# Processor_Interface.net
KiCad netlist of a schematic drawn in Altium Designer
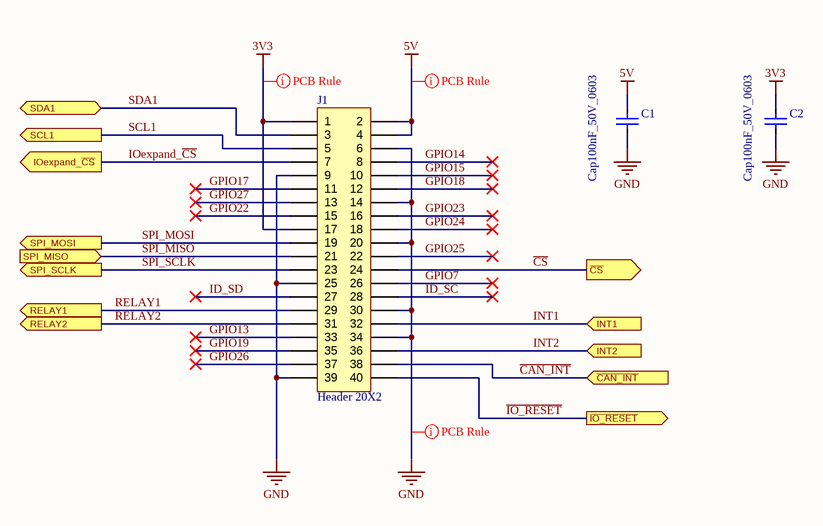
[diagram p0:  Processor_Interface.SchDoc]

(export (version "E")
  (design (tool "Eeschema 10.0.6"))
  (components
    (comp (ref "C1")
      (value "Cap100nF_50V_0603")
      (footprint "0603C_L")
      (libsource (lib "Advanced] Training Course - A365") (part "CAP General"))
    )
    (comp (ref "C2")
      (value "Cap100nF_50V_0603")
      (footprint "0603C_L")
      (libsource (lib "Advanced] Training Course - A365") (part "CAP General"))
    )
    (comp (ref "J1")
      (value "Header 20X2")
      (footprint "HDR2X20")
      (description "Header, 20-Pin, Dual row")
      (fields (field (name "PUBLISHER") "Altium Limited") (field (name "SOURCE") "WCT.SchLib"))
      (libsource (lib "Advanced] Training Course - A365") (part "Header 20X2"))
    )
  )
  (nets
    (net (code "1") (name "/CAN_INT") (class "Default")
      (node (ref "J1") (pin "38") (pinfunction "38_38") (pintype "passive"))
    )
    (net (code "2") (name "/GPIO7") (class "Default")
      (node (ref "J1") (pin "26") (pinfunction "26_26") (pintype "passive+no_connect"))
    )
    (net (code "3") (name "/GPIO13") (class "Default")
      (node (ref "J1") (pin "33") (pinfunction "33_33") (pintype "passive+no_connect"))
    )
    (net (code "4") (name "/GPIO14") (class "Default")
      (node (ref "J1") (pin "8") (pinfunction "8_8") (pintype "passive+no_connect"))
    )
    (net (code "5") (name "/GPIO15") (class "Default")
      (node (ref "J1") (pin "10") (pinfunction "10_10") (pintype "passive+no_connect"))
    )
    (net (code "6") (name "/GPIO17") (class "Default")
      (node (ref "J1") (pin "11") (pinfunction "11_11") (pintype "passive+no_connect"))
    )
    (net (code "7") (name "/GPIO18") (class "Default")
      (node (ref "J1") (pin "12") (pinfunction "12_12") (pintype "passive+no_connect"))
    )
    (net (code "8") (name "/GPIO19") (class "Default")
      (node (ref "J1") (pin "35") (pinfunction "35_35") (pintype "passive+no_connect"))
    )
    (net (code "9") (name "/GPIO22") (class "Default")
      (node (ref "J1") (pin "15") (pinfunction "15_15") (pintype "passive+no_connect"))
    )
    (net (code "10") (name "/GPIO23") (class "Default")
      (node (ref "J1") (pin "16") (pinfunction "16_16") (pintype "passive+no_connect"))
    )
    (net (code "11") (name "/GPIO24") (class "Default")
      (node (ref "J1") (pin "18") (pinfunction "18_18") (pintype "passive+no_connect"))
    )
    (net (code "12") (name "/GPIO25") (class "Default")
      (node (ref "J1") (pin "22") (pinfunction "22_22") (pintype "passive+no_connect"))
    )
    (net (code "13") (name "/GPIO26") (class "Default")
      (node (ref "J1") (pin "37") (pinfunction "37_37") (pintype "passive+no_connect"))
    )
    (net (code "14") (name "/GPIO27") (class "Default")
      (node (ref "J1") (pin "13") (pinfunction "13_13") (pintype "passive+no_connect"))
    )
    (net (code "15") (name "/ID_SC") (class "Default")
      (node (ref "J1") (pin "28") (pinfunction "28_28") (pintype "passive+no_connect"))
    )
    (net (code "16") (name "/ID_SD") (class "Default")
      (node (ref "J1") (pin "27") (pinfunction "27_27") (pintype "passive+no_connect"))
    )
    (net (code "17") (name "/INT1") (class "Default")
      (node (ref "J1") (pin "32") (pinfunction "32_32") (pintype "passive"))
    )
    (net (code "18") (name "/INT2") (class "Default")
      (node (ref "J1") (pin "36") (pinfunction "36_36") (pintype "passive"))
    )
    (net (code "19") (name "/IO_RESET") (class "Default")
      (node (ref "J1") (pin "40") (pinfunction "40_40") (pintype "passive"))
    )
    (net (code "20") (name "/IOexpand_~{CS}") (class "Default")
      (node (ref "J1") (pin "7") (pinfunction "7_7") (pintype "passive"))
    )
    (net (code "21") (name "/RELAY1") (class "Default")
      (node (ref "J1") (pin "29") (pinfunction "29_29") (pintype "passive"))
    )
    (net (code "22") (name "/RELAY2") (class "Default")
      (node (ref "J1") (pin "31") (pinfunction "31_31") (pintype "passive"))
    )
    (net (code "23") (name "/SCL1") (class "Default")
      (node (ref "J1") (pin "5") (pinfunction "5_5") (pintype "passive"))
    )
    (net (code "24") (name "/SDA1") (class "Default")
      (node (ref "J1") (pin "3") (pinfunction "3_3") (pintype "passive"))
    )
    (net (code "25") (name "/SPI_MISO") (class "Default")
      (node (ref "J1") (pin "21") (pinfunction "21_21") (pintype "passive"))
    )
    (net (code "26") (name "/SPI_MOSI") (class "Default")
      (node (ref "J1") (pin "19") (pinfunction "19_19") (pintype "passive"))
    )
    (net (code "27") (name "/SPI_SCLK") (class "Default")
      (node (ref "J1") (pin "23") (pinfunction "23_23") (pintype "passive"))
    )
    (net (code "28") (name "/~{CS}") (class "Default")
      (node (ref "J1") (pin "24") (pinfunction "24_24") (pintype "passive"))
    )
    (net (code "29") (name "3V3") (class "Default")
      (node (ref "C2") (pin "2") (pinfunction "2_2") (pintype "passive"))
      (node (ref "J1") (pin "1") (pinfunction "1_1") (pintype "passive"))
      (node (ref "J1") (pin "17") (pinfunction "17_17") (pintype "passive"))
    )
    (net (code "30") (name "5V") (class "Default")
      (node (ref "C1") (pin "2") (pinfunction "2_2") (pintype "passive"))
      (node (ref "J1") (pin "2") (pinfunction "2_2") (pintype "passive"))
      (node (ref "J1") (pin "4") (pinfunction "4_4") (pintype "passive"))
    )
    (net (code "31") (name "GND") (class "Default")
      (node (ref "C1") (pin "1") (pinfunction "1_1") (pintype "passive"))
      (node (ref "C2") (pin "1") (pinfunction "1_1") (pintype "passive"))
      (node (ref "J1") (pin "14") (pinfunction "14_14") (pintype "passive"))
      (node (ref "J1") (pin "20") (pinfunction "20_20") (pintype "passive"))
      (node (ref "J1") (pin "25") (pinfunction "25_25") (pintype "passive"))
      (node (ref "J1") (pin "30") (pinfunction "30_30") (pintype "passive"))
      (node (ref "J1") (pin "34") (pinfunction "34_34") (pintype "passive"))
      (node (ref "J1") (pin "39") (pinfunction "39_39") (pintype "passive"))
      (node (ref "J1") (pin "6") (pinfunction "6_6") (pintype "passive"))
      (node (ref "J1") (pin "9") (pinfunction "9_9") (pintype "passive"))
    )
  )
)
